# 1_Power_Path.net
KiCad netlist of a schematic drawn in Altium Designer
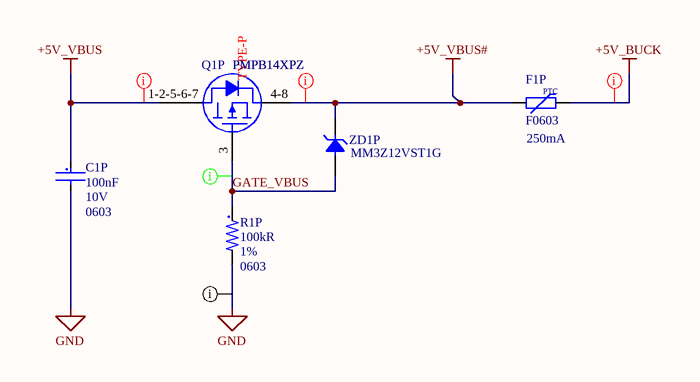
[diagram p0: 1_Power_Path.SchDoc]

(export (version "E")
  (design (tool "Eeschema 10.0.6"))
  (components
    (comp (ref "C1P")
      (value "100nF")
      (footprint "C0603-IPC_C_No_Silk")
      (description "Multilayer Ceramic Capacitor, 0.1 uF, 10 V, ± 10%, X7R, 0603 [1608 Metric]")
      (fields
        (field (name "MANUFACTURER PART NUMBER") "C0603C104K8RACTU")
        (field (name "MANUFACTURER") "KEMET")
        (field (name "VOLTAGE") "10V")
        (field (name "CASE/PACKAGE") "0603")
      )
      (libsource (lib "Lib_Capacitor_0603") (part "100nF_10V"))
    )
    (comp (ref "F1P")
      (value "F0603")
      (footprint "R0603-MFG")
      (description "Fuse PPTC SMD 0603")
      (fields (field (name "ALTIUM_VALUE") "250mA"))
      (libsource (lib "Lib_Fuse") (part "FUSE_PPTC_0603"))
    )
    (comp (ref "Q1P")
      (value "PMPB14XPZ")
      (footprint "DFN2020MD-MFG")
      (fields (field (name "MANUFACTURER") "Nexperia") (field (name "MANUFACTURER PART NUMBER") "PMPB14XPZ"))
      (libsource (lib "Lib_Mosfet_PNP") (part "PMPB14XPZ"))
    )
    (comp (ref "R1P")
      (value "100kR")
      (footprint "R0603-MFG")
      (description "SMD Chip Resistor, 100 kOhm, ± 1%, 100 mW, 0603 [1608 Metric], Thick Film, General Purpose")
      (fields
        (field (name "MANUFACTURER") "Yageo")
        (field (name "MANUFACTURER PART NUMBER") "AC0603FR-07100KL")
        (field (name "TOLERANCE") "1%")
        (field (name "CASE/PACKAGE") "0603")
      )
      (libsource (lib "Lib_Register_0603") (part "100K"))
    )
    (comp (ref "ZD1P")
      (value "MM3Z12VST1G")
      (footprint "SOD-323")
      (description "MM3Z12VST1G Zener Diode, 12V 2% 200 mW SMT 2-Pin SOD-323 ¦ ON Semiconductor MM3Z12VST1G")
      (fields (field (name "MANUFACTURER") "ON Semiconductor") (field (name "TOLERANCE") "2%"))
      (libsource (lib "Lib_Diodes") (part "MM3Z12VST1G"))
    )
  )
  (nets
    (net (code "1") (name "+5V_BUCK") (class "Default")
      (node (ref "F1P") (pin "2") (pinfunction "2_2") (pintype "passive"))
    )
    (net (code "2") (name "+5V_VBUS") (class "Default")
      (node (ref "C1P") (pin "1") (pinfunction "1_1") (pintype "passive"))
      (node (ref "Q1P") (pin "1-2-5-6-7") (pinfunction "D_1-2-5-6-7") (pintype "passive"))
    )
    (net (code "3") (name "+5V_VBUS#") (class "Default")
      (node (ref "F1P") (pin "1") (pinfunction "1_1") (pintype "passive"))
      (node (ref "Q1P") (pin "4-8") (pinfunction "S_4-8") (pintype "passive"))
      (node (ref "ZD1P") (pin "1") (pinfunction "C_1") (pintype "passive"))
    )
    (net (code "4") (name "/GATE_VBUS") (class "Default")
      (node (ref "Q1P") (pin "3") (pinfunction "G_3") (pintype "passive"))
      (node (ref "R1P") (pin "1") (pinfunction "1_1") (pintype "passive"))
      (node (ref "ZD1P") (pin "2") (pinfunction "A_2") (pintype "passive"))
    )
    (net (code "5") (name "GND") (class "Default")
      (node (ref "C1P") (pin "2") (pinfunction "2_2") (pintype "passive"))
      (node (ref "R1P") (pin "2") (pinfunction "2_2") (pintype "passive"))
    )
  )
)
